# Voeding.net
KiCad netlist of a schematic drawn in Altium Designer
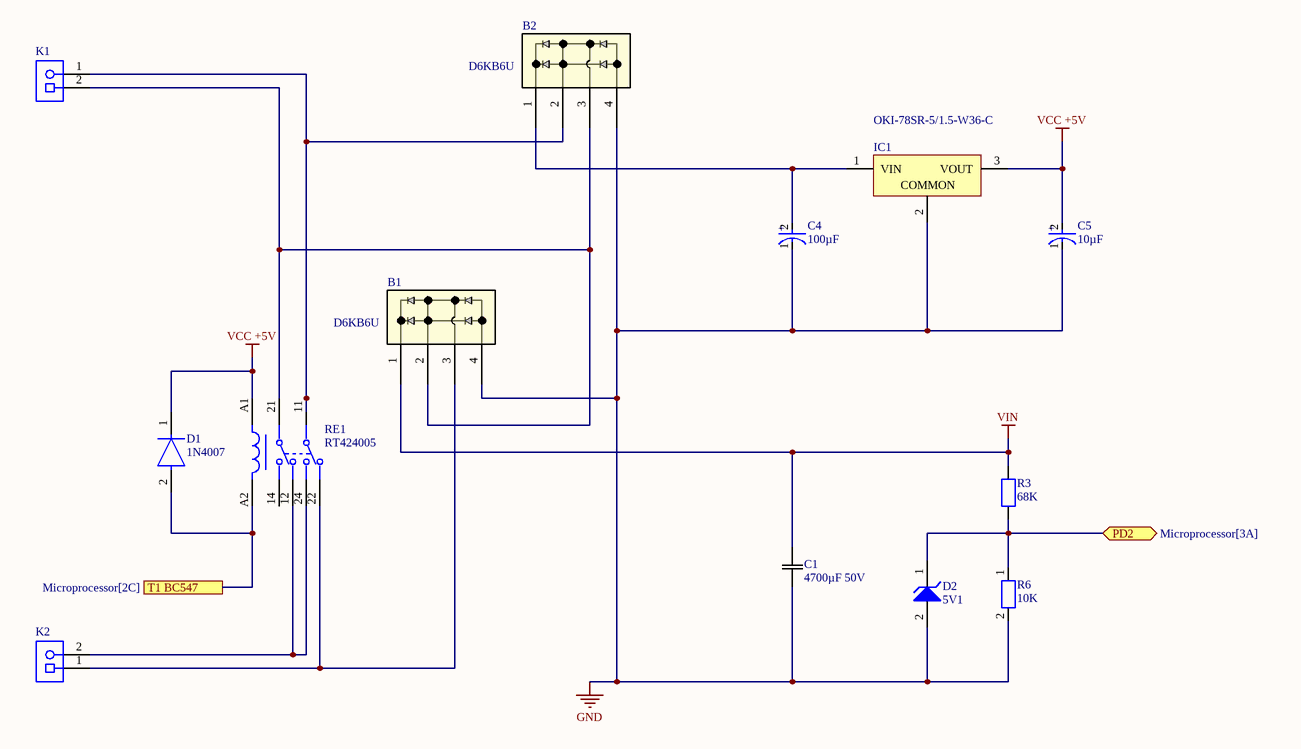
[diagram p0: Voeding.SchDoc]

(export (version "E")
  (design (tool "Eeschema 10.0.6"))
  (components
    (comp (ref "B1")
      (value "D6KB6U")
      (footprint "SIP4_D6K_MTC")
      (description "No Description Available")
      (fields (field (name "COPYRIGHT") "Copyright (C) 2023 Ultra Librarian. All rights reserved."))
      (libsource (lib "soldeerstation") (part "D6KB6U"))
    )
    (comp (ref "B2")
      (value "D6KB6U")
      (footprint "SIP4_D6K_MTC")
      (description "No Description Available")
      (fields (field (name "COPYRIGHT") "Copyright (C) 2023 Ultra Librarian. All rights reserved."))
      (libsource (lib "soldeerstation") (part "D6KB6U"))
    )
    (comp (ref "C1")
      (value "4700µF 50V")
      (footprint "CAP_Condensator_22X41")
      (description "22x40")
      (fields
        (field (name "MANUFACTURER_PART_NUMBER") "EETHC1H472HJ")
        (field (name "COPYRIGHT") "Copyright (C) 2023 Ultra Librarian. All rights reserved.")
      )
      (libsource (lib "soldeerstation") (part "4700µF 50V 22X40"))
    )
    (comp (ref "C4")
      (value "100µF")
      (footprint "Cap 50V 100µF 8X11")
      (description "Aluminum Electrolytic Capacitors (Radial Lead Type) AEC-Q200 Qualified 100uF ±20% 50V")
      (fields (field (name "VOLTAGE") "50V") (field (name "TOLERANCE") "20%"))
      (libsource (lib "soldeerstation") (part "Cap 50V 100µF 8x11"))
    )
    (comp (ref "C5")
      (value "10µF")
      (footprint "cap 10µF 50V")
      (description "Aluminum Electrolytic Capacitors (Radial Lead Type) 10uF ±20% 50V")
      (fields (field (name "TOLERANCE") "20%") (field (name "VOLTAGE") "50V"))
      (libsource (lib "soldeerstation") (part "10µF 50V"))
    )
    (comp (ref "D1")
      (value "1N4007")
      (footprint "1N4007")
      (description "Rectifier diode 1000 V 1 A DO-41, ,")
      (fields
        (field (name "MANUFACTURER") "Diotec")
        (field (name "OCTOPART") "https://octopart.com/1n4007-diotec-4040411")
      )
      (libsource (lib "soldeerstation") (part "1N4007"))
    )
    (comp (ref "D2")
      (value "5V1")
      (footprint "1N4007")
      (description "Zener Voltage Regulator, 500 mW, 2-Pin SOD-123, Pb-Free, Tape and Reel")
      (fields (field (name "PARTNUMBER") "MMSZ4689T1G") (field (name "MANUFACTURER") "On Semiconductor"))
      (libsource (lib "soldeerstation") (part "Zenerdiode"))
    )
    (comp (ref "IC1")
      (value "OKI-78SR-5/1.5-W36-C")
      (footprint "IC1")
      (description "Non-Isolated DC/DC Converter, 7.5 W, 7 to 36 V, 1.5 A, -40 to 85 degC, 3-Pin THD, RoHS")
      (fields (field (name "MANUFACTURER") "Murata"))
      (libsource (lib "soldeerstation") (part "IC1"))
    )
    (comp (ref "K1")
      (value "1729128")
      (footprint "2pin connector")
      (description "PCB Terminal Block, 13.5 A, 400 V, 2-Pin THD, RoHS, Bulk")
      (fields (field (name "MANUFACTURER") "Phoenix Contact"))
      (libsource (lib "soldeerstation") (part "2pin connector"))
    )
    (comp (ref "K2")
      (value "1729128")
      (footprint "2pin connector")
      (description "PCB Terminal Block, 13.5 A, 400 V, 2-Pin THD, RoHS, Bulk")
      (fields (field (name "MANUFACTURER") "Phoenix Contact"))
      (libsource (lib "") (part "2pin connector_1"))
    )
    (comp (ref "R3")
      (value "68K")
      (footprint "Weerstand 1M ohm")
      (fields (field (name "MANUFACTURER") "Vishay Dale") (field (name "PART NUMBER") "CRCW080568K0FKEA"))
      (libsource (lib "soldeerstation") (part "Weerstand 68k ohm"))
    )
    (comp (ref "R6")
      (value "10K")
      (footprint "Weerstand 1M ohm")
      (description "RES Thick Film, 10kΩ, 1%, 0.125W, 100ppm/°C, 0805")
      (fields (field (name "TOLERANCE") "1%"))
      (libsource (lib "soldeerstation") (part "Weerstand 10K ohm"))
    )
    (comp (ref "RE1")
      (value "RT424005")
      (footprint "Vermogenrelais")
      (description "RELAY GENERAL PURPOSE DPDT 8A 5V")
      (fields
        (field (name "OCTOPART") "https://octopart.com/5-1393243-9-te+connectivity-41835766")
        (field (name "MANUFACTURER") "TE Connectivity")
      )
      (libsource (lib "soldeerstation") (part "Vermogenrelais"))
    )
  )
  (nets
    (net (code "1") (name "/PD2") (class "Default")
      (node (ref "D2") (pin "1") (pinfunction "K_1") (pintype "passive"))
      (node (ref "R3") (pin "2") (pinfunction "2_2") (pintype "passive"))
      (node (ref "R6") (pin "1") (pinfunction "1_1") (pintype "passive"))
    )
    (net (code "2") (name "/T1 BC547") (class "Default")
      (node (ref "D1") (pin "2") (pinfunction "A_2") (pintype "passive"))
      (node (ref "RE1") (pin "A2") (pinfunction "A2_A2") (pintype "passive"))
    )
    (net (code "3") (name "GND") (class "Default")
      (node (ref "B1") (pin "4") (pinfunction "4_4") (pintype "passive"))
      (node (ref "B2") (pin "4") (pinfunction "4_4") (pintype "passive"))
      (node (ref "C1") (pin "1") (pinfunction "1_1") (pintype "passive"))
      (node (ref "C4") (pin "1") (pinfunction "C_1") (pintype "passive"))
      (node (ref "C5") (pin "1") (pinfunction "C_1") (pintype "passive"))
      (node (ref "D2") (pin "2") (pinfunction "A_2") (pintype "passive"))
      (node (ref "IC1") (pin "2") (pinfunction "COMMON_2") (pintype "power_in"))
      (node (ref "R6") (pin "2") (pinfunction "2_2") (pintype "passive"))
    )
    (net (code "4") (name "Net-(B1-Pad2)") (class "Default")
      (node (ref "B1") (pin "2") (pinfunction "2_2") (pintype "passive"))
      (node (ref "B2") (pin "3") (pinfunction "3_3") (pintype "passive"))
      (node (ref "K1") (pin "2") (pinfunction "2_2") (pintype "passive"))
      (node (ref "RE1") (pin "21") (pinfunction "21_21") (pintype "passive"))
    )
    (net (code "5") (name "Net-(B1-Pad3)") (class "Default")
      (node (ref "B1") (pin "3") (pinfunction "3_3") (pintype "passive"))
      (node (ref "K2") (pin "1") (pinfunction "1_1") (pintype "passive"))
      (node (ref "RE1") (pin "22") (pinfunction "22_22") (pintype "passive"))
    )
    (net (code "6") (name "Net-(B2-Pad2)") (class "Default")
      (node (ref "B2") (pin "2") (pinfunction "2_2") (pintype "passive"))
      (node (ref "K1") (pin "1") (pinfunction "1_1") (pintype "passive"))
      (node (ref "RE1") (pin "11") (pinfunction "11_11") (pintype "passive"))
    )
    (net (code "7") (name "Net-(C4-A)") (class "Default")
      (node (ref "B2") (pin "1") (pinfunction "1_1") (pintype "passive"))
      (node (ref "C4") (pin "2") (pinfunction "A_2") (pintype "passive"))
      (node (ref "IC1") (pin "1") (pinfunction "VIN_1") (pintype "power_in"))
    )
    (net (code "8") (name "Net-(K2-Pad2)") (class "Default")
      (node (ref "K2") (pin "2") (pinfunction "2_2") (pintype "passive"))
      (node (ref "RE1") (pin "12") (pinfunction "12_12") (pintype "passive"))
      (node (ref "RE1") (pin "24") (pinfunction "24_24") (pintype "passive"))
    )
    (net (code "9") (name "VCC +5V") (class "Default")
      (node (ref "C5") (pin "2") (pinfunction "A_2") (pintype "passive"))
      (node (ref "D1") (pin "1") (pinfunction "C_1") (pintype "passive"))
      (node (ref "IC1") (pin "3") (pinfunction "VOUT_3") (pintype "power_in"))
      (node (ref "RE1") (pin "A1") (pinfunction "A1_A1") (pintype "passive"))
    )
    (net (code "10") (name "VIN") (class "Default")
      (node (ref "B1") (pin "1") (pinfunction "1_1") (pintype "passive"))
      (node (ref "C1") (pin "2") (pinfunction "2_2") (pintype "passive"))
      (node (ref "R3") (pin "1") (pinfunction "1_1") (pintype "passive"))
    )
    (net (code "11") (name "unconnected-(RE1-Pad14)") (class "Default")
      (node (ref "RE1") (pin "14") (pinfunction "14_14") (pintype "passive"))
    )
  )
)
